# right_revision2_0.net
KiCad netlist of a schematic drawn in EAGLE
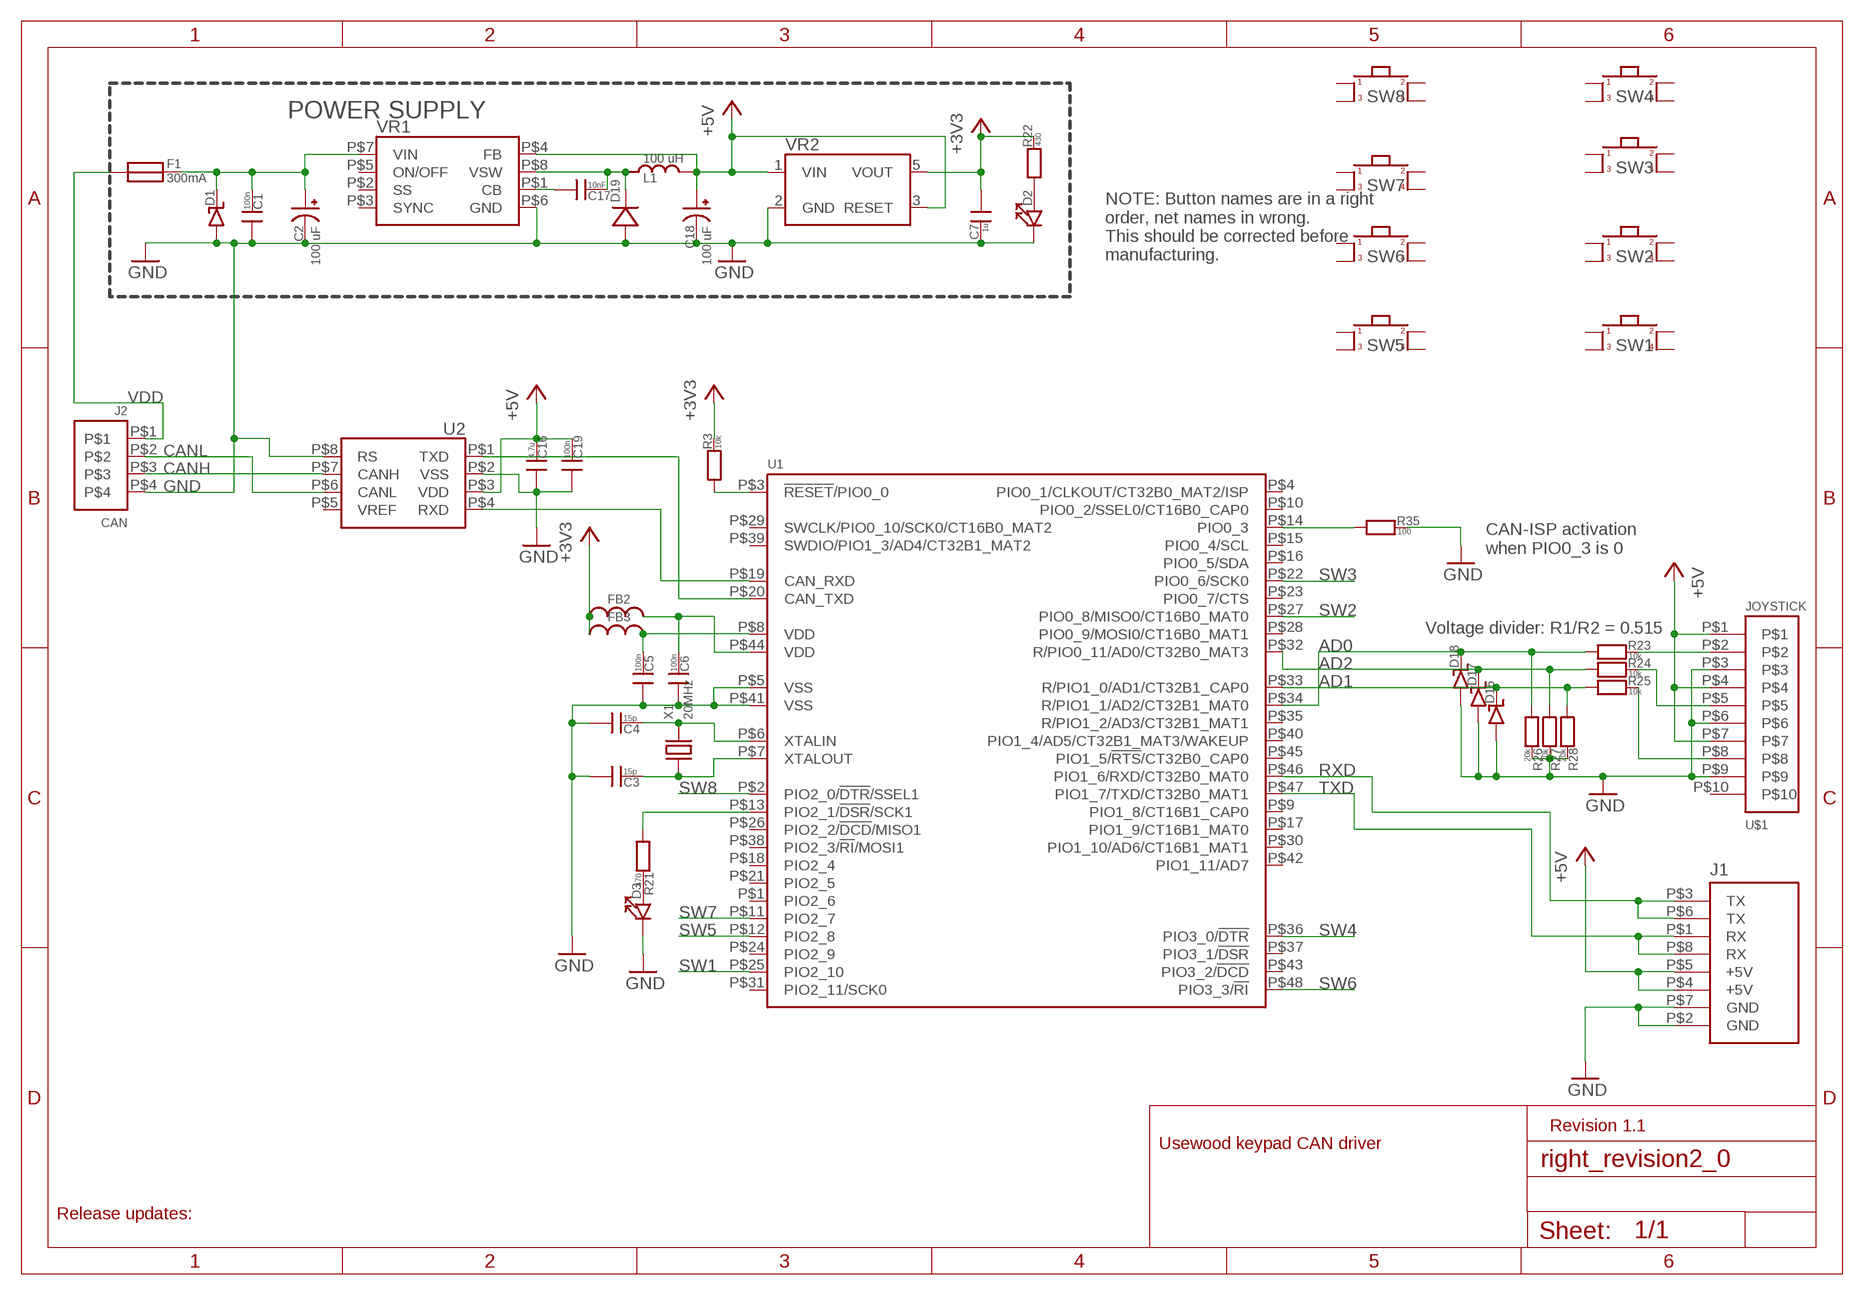
[diagram p0: schematic, sheet 1]

(export (version "E")
  (design (tool "Eeschema 10.0.6"))
  (components
    (comp (ref "C1")
      (value "100n")
      (footprint "eagle-import:0603_SILKSCREEN")
      (libsource (lib "eagle-import") (part "CAP0603_SILKSCREEN"))
    )
    (comp (ref "C2")
      (value "100 uF")
      (footprint "eagle-import:CAP_POL_SMD_10X10X10MM")
      (libsource (lib "eagle-import") (part "CAP_POLSMD_10X10X10MM"))
    )
    (comp (ref "C3")
      (value "15p")
      (footprint "eagle-import:0603_SILKSCREEN")
      (libsource (lib "eagle-import") (part "CAP0603_SILKSCREEN"))
    )
    (comp (ref "C4")
      (value "15p")
      (footprint "eagle-import:0603_SILKSCREEN")
      (libsource (lib "eagle-import") (part "CAP0603_SILKSCREEN"))
    )
    (comp (ref "C5")
      (value "100n")
      (footprint "eagle-import:0603_SILKSCREEN")
      (libsource (lib "eagle-import") (part "CAP0603_SILKSCREEN"))
    )
    (comp (ref "C6")
      (value "100n")
      (footprint "eagle-import:0603_SILKSCREEN")
      (libsource (lib "eagle-import") (part "CAP0603_SILKSCREEN"))
    )
    (comp (ref "C7")
      (value "1u")
      (footprint "eagle-import:0603_SILKSCREEN")
      (libsource (lib "eagle-import") (part "CAP0603_SILKSCREEN"))
    )
    (comp (ref "C16")
      (value "4.7u")
      (footprint "eagle-import:0603_SILKSCREEN")
      (libsource (lib "eagle-import") (part "CAP0603_SILKSCREEN"))
    )
    (comp (ref "C17")
      (value "10nF")
      (footprint "eagle-import:0603_SILKSCREEN")
      (libsource (lib "eagle-import") (part "CAP0603_SILKSCREEN"))
    )
    (comp (ref "C18")
      (value "100 uF")
      (footprint "eagle-import:CAP_POL_SMD_10X10X10MM")
      (libsource (lib "eagle-import") (part "CAP_POLSMD_10X10X10MM"))
    )
    (comp (ref "C19")
      (value "100n")
      (footprint "eagle-import:0603_SILKSCREEN")
      (libsource (lib "eagle-import") (part "CAP0603_SILKSCREEN"))
    )
    (comp (ref "D1")
      (value "DIODE_TVSDO-214AA")
      (footprint "eagle-import:DO-214AB")
      (libsource (lib "eagle-import") (part "DIODE_TVSDO-214AA"))
    )
    (comp (ref "D2")
      (value "LED0603_SILKSCREEN")
      (footprint "eagle-import:0603_SILKSCREEN")
      (libsource (lib "eagle-import") (part "LED0603_SILKSCREEN"))
    )
    (comp (ref "D3")
      (value "LED0603_SILKSCREEN")
      (footprint "eagle-import:0603_SILKSCREEN")
      (libsource (lib "eagle-import") (part "LED0603_SILKSCREEN"))
    )
    (comp (ref "D16")
      (value "DIODE_ZENERSDO123")
      (footprint "eagle-import:SOD123")
      (libsource (lib "eagle-import") (part "DIODE_ZENERSDO123"))
    )
    (comp (ref "D17")
      (value "DIODE_ZENERSDO123")
      (footprint "eagle-import:SOD123")
      (libsource (lib "eagle-import") (part "DIODE_ZENERSDO123"))
    )
    (comp (ref "D18")
      (value "DIODE_ZENERSDO123")
      (footprint "eagle-import:SOD123")
      (libsource (lib "eagle-import") (part "DIODE_ZENERSDO123"))
    )
    (comp (ref "D19")
      (value "DIODEDO219AB")
      (footprint "eagle-import:DO219AB")
      (libsource (lib "eagle-import") (part "DIODEDO219AB"))
    )
    (comp (ref "F1")
      (value "300mA")
      (footprint "eagle-import:FUSE_100MA")
      (libsource (lib "eagle-import") (part "FUSE100MA"))
    )
    (comp (ref "FB2")
      (value "FERRITE0603_SILKSCREEN")
      (footprint "eagle-import:0603_SILKSCREEN")
      (libsource (lib "eagle-import") (part "FERRITE0603_SILKSCREEN"))
    )
    (comp (ref "FB3")
      (value "FERRITE0603_SILKSCREEN")
      (footprint "eagle-import:0603_SILKSCREEN")
      (libsource (lib "eagle-import") (part "FERRITE0603_SILKSCREEN"))
    )
    (comp (ref "J1")
      (value "HEADER_USART_2_TH")
      (footprint "eagle-import:HEADER_USART_2_TH")
      (libsource (lib "eagle-import") (part "HEADER_USART_2_TH"))
    )
    (comp (ref "J2")
      (value "CAN")
      (footprint "eagle-import:MOLEX_MICRO-FIT_4WAY")
      (libsource (lib "eagle-import") (part "MOLEX_MICRO-FIT_4WAYTH"))
    )
    (comp (ref "L1")
      (value "100 uH")
      (footprint "eagle-import:INDUCTOR_BOURNS_10X13X5MM")
      (libsource (lib "eagle-import") (part "INDUCTORBOURNS_10X13X5MM"))
    )
    (comp (ref "R3")
      (value "10k")
      (footprint "eagle-import:0603_SILKSCREEN")
      (libsource (lib "eagle-import") (part "RES0604_SILKSCREEN"))
    )
    (comp (ref "R21")
      (value "470")
      (footprint "eagle-import:0603_SILKSCREEN")
      (libsource (lib "eagle-import") (part "RES0604_SILKSCREEN"))
    )
    (comp (ref "R22")
      (value "430")
      (footprint "eagle-import:0603_SILKSCREEN")
      (libsource (lib "eagle-import") (part "RES0604_SILKSCREEN"))
    )
    (comp (ref "R23")
      (value "10k")
      (footprint "eagle-import:0603_SILKSCREEN")
      (libsource (lib "eagle-import") (part "RES0604_SILKSCREEN"))
    )
    (comp (ref "R24")
      (value "10k")
      (footprint "eagle-import:0603_SILKSCREEN")
      (libsource (lib "eagle-import") (part "RES0604_SILKSCREEN"))
    )
    (comp (ref "R25")
      (value "10k")
      (footprint "eagle-import:0603_SILKSCREEN")
      (libsource (lib "eagle-import") (part "RES0604_SILKSCREEN"))
    )
    (comp (ref "R26")
      (value "20k")
      (footprint "eagle-import:0603_SILKSCREEN")
      (libsource (lib "eagle-import") (part "RES0604_SILKSCREEN"))
    )
    (comp (ref "R27")
      (value "20k")
      (footprint "eagle-import:0603_SILKSCREEN")
      (libsource (lib "eagle-import") (part "RES0604_SILKSCREEN"))
    )
    (comp (ref "R28")
      (value "20k")
      (footprint "eagle-import:0603_SILKSCREEN")
      (libsource (lib "eagle-import") (part "RES0604_SILKSCREEN"))
    )
    (comp (ref "R35")
      (value "100")
      (footprint "eagle-import:0603_SILKSCREEN")
      (libsource (lib "eagle-import") (part "RES0604_SILKSCREEN"))
    )
    (comp (ref "SW1")
      (value "SWITCH_EVQP6L")
      (footprint "eagle-import:SWITCH_EVQ9P6B40")
      (libsource (lib "eagle-import") (part "SWITCH_EVQP6L"))
    )
    (comp (ref "SW2")
      (value "SWITCH_EVQP6L")
      (footprint "eagle-import:SWITCH_EVQ9P6B40")
      (libsource (lib "eagle-import") (part "SWITCH_EVQP6L"))
    )
    (comp (ref "SW3")
      (value "SWITCH_EVQP6L")
      (footprint "eagle-import:SWITCH_EVQ9P6B40")
      (libsource (lib "eagle-import") (part "SWITCH_EVQP6L"))
    )
    (comp (ref "SW4")
      (value "SWITCH_EVQP6L")
      (footprint "eagle-import:SWITCH_EVQ9P6B40")
      (libsource (lib "eagle-import") (part "SWITCH_EVQP6L"))
    )
    (comp (ref "SW5")
      (value "SWITCH_EVQP6L")
      (footprint "eagle-import:SWITCH_EVQ9P6B40")
      (libsource (lib "eagle-import") (part "SWITCH_EVQP6L"))
    )
    (comp (ref "SW6")
      (value "SWITCH_EVQP6L")
      (footprint "eagle-import:SWITCH_EVQ9P6B40")
      (libsource (lib "eagle-import") (part "SWITCH_EVQP6L"))
    )
    (comp (ref "SW7")
      (value "SWITCH_EVQP6L")
      (footprint "eagle-import:SWITCH_EVQ9P6B40")
      (libsource (lib "eagle-import") (part "SWITCH_EVQP6L"))
    )
    (comp (ref "SW8")
      (value "SWITCH_EVQP6L")
      (footprint "eagle-import:SWITCH_EVQ9P6B40")
      (libsource (lib "eagle-import") (part "SWITCH_EVQP6L"))
    )
    (comp (ref "U$1")
      (value "JOYSTICK")
      (footprint "eagle-import:MOLEX-MICRO-FIT_10WAY")
      (libsource (lib "eagle-import") (part "MOLEX_MICRO-FIT_10WAYTH"))
    )
    (comp (ref "U1")
      (value "LPC11C14_QFP48")
      (footprint "eagle-import:QFP48")
      (libsource (lib "eagle-import") (part "LPC11C14_QFP48"))
    )
    (comp (ref "U2")
      (value "MCP2551_SOIC8")
      (footprint "eagle-import:SOIC8")
      (libsource (lib "eagle-import") (part "MCP2551_SOIC8"))
    )
    (comp (ref "VR1")
      (value "LM2671SOIC8")
      (footprint "eagle-import:SOIC8")
      (libsource (lib "eagle-import") (part "LM2671SOIC8"))
    )
    (comp (ref "VR2")
      (value "LP2985SOP5")
      (footprint "eagle-import:SOP5")
      (libsource (lib "eagle-import") (part "LP2985SOP5"))
    )
    (comp (ref "X1")
      (value "20MHz")
      (footprint "eagle-import:XTAL_SMD_5X3.2")
      (libsource (lib "eagle-import") (part "XTALSMD_5X3.2"))
    )
  )
  (nets
    (net (code "1") (name "+3V3") (class "Default")
      (node (ref "C7") (pin "0") (pinfunction "P$1_0") (pintype "bidirectional"))
      (node (ref "FB2") (pin "0") (pinfunction "P$1_0") (pintype "bidirectional"))
      (node (ref "FB3") (pin "0") (pinfunction "P$1_0") (pintype "bidirectional"))
      (node (ref "R22") (pin "1") (pinfunction "P$2_1") (pintype "bidirectional"))
      (node (ref "R3") (pin "1") (pinfunction "P$2_1") (pintype "bidirectional"))
      (node (ref "VR2") (pin "5") (pinfunction "VOUT_5") (pintype "bidirectional"))
    )
    (net (code "2") (name "+5V") (class "Default")
      (node (ref "C16") (pin "1") (pinfunction "P$2_1") (pintype "bidirectional"))
      (node (ref "C18") (pin "+") (pinfunction "+_+") (pintype "bidirectional"))
      (node (ref "C19") (pin "1") (pinfunction "P$2_1") (pintype "bidirectional"))
      (node (ref "J1") (pin "P$4") (pinfunction "+5V_P$4") (pintype "bidirectional"))
      (node (ref "J1") (pin "P$5") (pinfunction "+5V_P$5") (pintype "bidirectional"))
      (node (ref "L1") (pin "P$2") (pinfunction "P$2_P$2") (pintype "bidirectional"))
      (node (ref "U$1") (pin "P$1") (pinfunction "P$1_P$1") (pintype "bidirectional"))
      (node (ref "U$1") (pin "P$4") (pinfunction "P$4_P$4") (pintype "bidirectional"))
      (node (ref "U$1") (pin "P$7") (pinfunction "P$7_P$7") (pintype "bidirectional"))
      (node (ref "U2") (pin "P$3") (pinfunction "VDD_P$3") (pintype "bidirectional"))
      (node (ref "VR1") (pin "P$4") (pinfunction "FB_P$4") (pintype "bidirectional"))
      (node (ref "VR2") (pin "1") (pinfunction "VIN_1") (pintype "bidirectional"))
      (node (ref "VR2") (pin "3") (pinfunction "RESET_3") (pintype "bidirectional"))
    )
    (net (code "3") (name "/AD0") (class "Default")
      (node (ref "D18") (pin "P$2") (pinfunction "N_P$2") (pintype "bidirectional"))
      (node (ref "R23") (pin "0") (pinfunction "P$1_0") (pintype "bidirectional"))
      (node (ref "R26") (pin "0") (pinfunction "P$1_0") (pintype "bidirectional"))
      (node (ref "U1") (pin "P$34") (pinfunction "R/PIO1_1/AD2/CT32B1_MAT0_P$34") (pintype "bidirectional"))
    )
    (net (code "4") (name "/AD1") (class "Default")
      (node (ref "D16") (pin "P$2") (pinfunction "N_P$2") (pintype "bidirectional"))
      (node (ref "R25") (pin "0") (pinfunction "P$1_0") (pintype "bidirectional"))
      (node (ref "R28") (pin "0") (pinfunction "P$1_0") (pintype "bidirectional"))
      (node (ref "U1") (pin "P$33") (pinfunction "R/PIO1_0/AD1/CT32B1_CAP0_P$33") (pintype "bidirectional"))
    )
    (net (code "5") (name "/AD2") (class "Default")
      (node (ref "D17") (pin "P$2") (pinfunction "N_P$2") (pintype "bidirectional"))
      (node (ref "R24") (pin "0") (pinfunction "P$1_0") (pintype "bidirectional"))
      (node (ref "R27") (pin "0") (pinfunction "P$1_0") (pintype "bidirectional"))
      (node (ref "U1") (pin "P$32") (pinfunction "R/PIO0_11/AD0/CT32B0_MAT3_P$32") (pintype "bidirectional"))
    )
    (net (code "6") (name "/CANH") (class "Default")
      (node (ref "J2") (pin "P$3") (pinfunction "P$3_P$3") (pintype "bidirectional"))
      (node (ref "U2") (pin "P$7") (pinfunction "CANH_P$7") (pintype "bidirectional"))
    )
    (net (code "7") (name "/CANL") (class "Default")
      (node (ref "J2") (pin "P$2") (pinfunction "P$2_P$2") (pintype "bidirectional"))
      (node (ref "U2") (pin "P$6") (pinfunction "CANL_P$6") (pintype "bidirectional"))
    )
    (net (code "8") (name "/RXD") (class "Default")
      (node (ref "J1") (pin "P$3") (pinfunction "TX_P$3") (pintype "bidirectional"))
      (node (ref "J1") (pin "P$6") (pinfunction "TX_P$6") (pintype "bidirectional"))
      (node (ref "U1") (pin "P$46") (pinfunction "PIO1_6/RXD/CT32B0_MAT0_P$46") (pintype "bidirectional"))
    )
    (net (code "9") (name "/SW1") (class "Default")
      (node (ref "U1") (pin "P$25") (pinfunction "PIO2_10_P$25") (pintype "bidirectional"))
    )
    (net (code "10") (name "/SW2") (class "Default")
      (node (ref "U1") (pin "P$27") (pinfunction "PIO0_8/MISO0/CT16B0_MAT0_P$27") (pintype "bidirectional"))
    )
    (net (code "11") (name "/SW3") (class "Default")
      (node (ref "U1") (pin "P$22") (pinfunction "PIO0_6/SCK0_P$22") (pintype "bidirectional"))
    )
    (net (code "12") (name "/SW4") (class "Default")
      (node (ref "U1") (pin "P$36") (pinfunction "PIO3_0/~{DTR}_P$36") (pintype "bidirectional"))
    )
    (net (code "13") (name "/SW5") (class "Default")
      (node (ref "U1") (pin "P$12") (pinfunction "PIO2_8_P$12") (pintype "bidirectional"))
    )
    (net (code "14") (name "/SW6") (class "Default")
      (node (ref "U1") (pin "P$48") (pinfunction "PIO3_3/~{RI}_P$48") (pintype "bidirectional"))
    )
    (net (code "15") (name "/SW7") (class "Default")
      (node (ref "U1") (pin "P$11") (pinfunction "PIO2_7_P$11") (pintype "bidirectional"))
    )
    (net (code "16") (name "/SW8") (class "Default")
      (node (ref "U1") (pin "P$2") (pinfunction "PIO2_0/~{DTR}/SSEL1_P$2") (pintype "bidirectional"))
    )
    (net (code "17") (name "/TXD") (class "Default")
      (node (ref "J1") (pin "P$1") (pinfunction "RX_P$1") (pintype "bidirectional"))
      (node (ref "J1") (pin "P$8") (pinfunction "RX_P$8") (pintype "bidirectional"))
      (node (ref "U1") (pin "P$47") (pinfunction "PIO1_7/TXD/CT32B0_MAT1_P$47") (pintype "bidirectional"))
    )
    (net (code "18") (name "/VDD") (class "Default")
      (node (ref "F1") (pin "P$1") (pinfunction "P$1_P$1") (pintype "bidirectional"))
      (node (ref "J2") (pin "P$1") (pinfunction "P$1_P$1") (pintype "bidirectional"))
    )
    (net (code "19") (name "GND") (class "Default")
      (node (ref "C1") (pin "0") (pinfunction "P$1_0") (pintype "bidirectional"))
      (node (ref "C16") (pin "0") (pinfunction "P$1_0") (pintype "bidirectional"))
      (node (ref "C18") (pin "-") (pinfunction "-_-") (pintype "bidirectional"))
      (node (ref "C19") (pin "0") (pinfunction "P$1_0") (pintype "bidirectional"))
      (node (ref "C2") (pin "-") (pinfunction "-_-") (pintype "bidirectional"))
      (node (ref "C3") (pin "0") (pinfunction "P$1_0") (pintype "bidirectional"))
      (node (ref "C4") (pin "0") (pinfunction "P$1_0") (pintype "bidirectional"))
      (node (ref "C5") (pin "0") (pinfunction "P$1_0") (pintype "bidirectional"))
      (node (ref "C6") (pin "0") (pinfunction "P$1_0") (pintype "bidirectional"))
      (node (ref "C7") (pin "1") (pinfunction "P$2_1") (pintype "bidirectional"))
      (node (ref "D1") (pin "P$1") (pinfunction "P_P$1") (pintype "bidirectional"))
      (node (ref "D16") (pin "P$1") (pinfunction "P_P$1") (pintype "bidirectional"))
      (node (ref "D17") (pin "P$1") (pinfunction "P_P$1") (pintype "bidirectional"))
      (node (ref "D18") (pin "P$1") (pinfunction "P_P$1") (pintype "bidirectional"))
      (node (ref "D19") (pin "P$1") (pinfunction "P_P$1") (pintype "bidirectional"))
      (node (ref "D2") (pin "1") (pinfunction "1_1") (pintype "bidirectional"))
      (node (ref "D3") (pin "1") (pinfunction "1_1") (pintype "bidirectional"))
      (node (ref "J1") (pin "P$2") (pinfunction "GND_P$2") (pintype "bidirectional"))
      (node (ref "J1") (pin "P$7") (pinfunction "GND_P$7") (pintype "bidirectional"))
      (node (ref "J2") (pin "P$4") (pinfunction "P$4_P$4") (pintype "bidirectional"))
      (node (ref "R26") (pin "1") (pinfunction "P$2_1") (pintype "bidirectional"))
      (node (ref "R27") (pin "1") (pinfunction "P$2_1") (pintype "bidirectional"))
      (node (ref "R28") (pin "1") (pinfunction "P$2_1") (pintype "bidirectional"))
      (node (ref "R35") (pin "1") (pinfunction "P$2_1") (pintype "bidirectional"))
      (node (ref "U$1") (pin "P$3") (pinfunction "P$3_P$3") (pintype "bidirectional"))
      (node (ref "U$1") (pin "P$6") (pinfunction "P$6_P$6") (pintype "bidirectional"))
      (node (ref "U$1") (pin "P$9") (pinfunction "P$9_P$9") (pintype "bidirectional"))
      (node (ref "U1") (pin "P$41") (pinfunction "VSS_P$41") (pintype "bidirectional"))
      (node (ref "U1") (pin "P$5") (pinfunction "VSS_P$5") (pintype "bidirectional"))
      (node (ref "U2") (pin "P$2") (pinfunction "VSS_P$2") (pintype "bidirectional"))
      (node (ref "U2") (pin "P$8") (pinfunction "RS_P$8") (pintype "bidirectional"))
      (node (ref "VR1") (pin "P$6") (pinfunction "GND_P$6") (pintype "bidirectional"))
      (node (ref "VR2") (pin "2") (pinfunction "GND_2") (pintype "bidirectional"))
    )
    (net (code "20") (name "Net-(C1-P$2)") (class "Default")
      (node (ref "C1") (pin "1") (pinfunction "P$2_1") (pintype "bidirectional"))
      (node (ref "C2") (pin "+") (pinfunction "+_+") (pintype "bidirectional"))
      (node (ref "D1") (pin "P$2") (pinfunction "N_P$2") (pintype "bidirectional"))
      (node (ref "F1") (pin "P$2") (pinfunction "P$2_P$2") (pintype "bidirectional"))
      (node (ref "VR1") (pin "P$7") (pinfunction "VIN_P$7") (pintype "bidirectional"))
    )
    (net (code "21") (name "Net-(C3-P$2)") (class "Default")
      (node (ref "C3") (pin "1") (pinfunction "P$2_1") (pintype "bidirectional"))
      (node (ref "U1") (pin "P$7") (pinfunction "XTALOUT_P$7") (pintype "bidirectional"))
      (node (ref "X1") (pin "P$1") (pinfunction "P$1_P$1") (pintype "bidirectional"))
    )
    (net (code "22") (name "Net-(C4-P$2)") (class "Default")
      (node (ref "C4") (pin "1") (pinfunction "P$2_1") (pintype "bidirectional"))
      (node (ref "U1") (pin "P$6") (pinfunction "XTALIN_P$6") (pintype "bidirectional"))
      (node (ref "X1") (pin "P$2") (pinfunction "P$2_P$2") (pintype "bidirectional"))
    )
    (net (code "23") (name "Net-(C5-P$2)") (class "Default")
      (node (ref "C5") (pin "1") (pinfunction "P$2_1") (pintype "bidirectional"))
      (node (ref "FB3") (pin "1") (pinfunction "P$2_1") (pintype "bidirectional"))
      (node (ref "U1") (pin "P$8") (pinfunction "VDD_P$8") (pintype "bidirectional"))
    )
    (net (code "24") (name "Net-(C6-P$2)") (class "Default")
      (node (ref "C6") (pin "1") (pinfunction "P$2_1") (pintype "bidirectional"))
      (node (ref "FB2") (pin "1") (pinfunction "P$2_1") (pintype "bidirectional"))
      (node (ref "U1") (pin "P$44") (pinfunction "VDD_P$44") (pintype "bidirectional"))
    )
    (net (code "25") (name "Net-(C17-P$1)") (class "Default")
      (node (ref "C17") (pin "0") (pinfunction "P$1_0") (pintype "bidirectional"))
      (node (ref "VR1") (pin "P$1") (pinfunction "CB_P$1") (pintype "bidirectional"))
    )
    (net (code "26") (name "Net-(C17-P$2)") (class "Default")
      (node (ref "C17") (pin "1") (pinfunction "P$2_1") (pintype "bidirectional"))
      (node (ref "D19") (pin "P$2") (pinfunction "N_P$2") (pintype "bidirectional"))
      (node (ref "L1") (pin "P$1") (pinfunction "P$1_P$1") (pintype "bidirectional"))
      (node (ref "VR1") (pin "P$8") (pinfunction "VSW_P$8") (pintype "bidirectional"))
    )
    (net (code "27") (name "Net-(R3-P$1)") (class "Default")
      (node (ref "R3") (pin "0") (pinfunction "P$1_0") (pintype "bidirectional"))
      (node (ref "U1") (pin "P$3") (pinfunction "~{RESET}/PIO0_0_P$3") (pintype "bidirectional"))
    )
    (net (code "28") (name "Net-(R21-P$1)") (class "Default")
      (node (ref "R21") (pin "0") (pinfunction "P$1_0") (pintype "bidirectional"))
      (node (ref "U1") (pin "P$13") (pinfunction "PIO2_1/~{DSR}/SCK1_P$13") (pintype "bidirectional"))
    )
    (net (code "29") (name "Net-(R21-P$2)") (class "Default")
      (node (ref "D3") (pin "0") (pinfunction "0_0") (pintype "bidirectional"))
      (node (ref "R21") (pin "1") (pinfunction "P$2_1") (pintype "bidirectional"))
    )
    (net (code "30") (name "Net-(R22-P$1)") (class "Default")
      (node (ref "D2") (pin "0") (pinfunction "0_0") (pintype "bidirectional"))
      (node (ref "R22") (pin "0") (pinfunction "P$1_0") (pintype "bidirectional"))
    )
    (net (code "31") (name "Net-(R23-P$2)") (class "Default")
      (node (ref "R23") (pin "1") (pinfunction "P$2_1") (pintype "bidirectional"))
      (node (ref "U$1") (pin "P$2") (pinfunction "P$2_P$2") (pintype "bidirectional"))
    )
    (net (code "32") (name "Net-(R24-P$2)") (class "Default")
      (node (ref "R24") (pin "1") (pinfunction "P$2_1") (pintype "bidirectional"))
      (node (ref "U$1") (pin "P$5") (pinfunction "P$5_P$5") (pintype "bidirectional"))
    )
    (net (code "33") (name "Net-(R25-P$2)") (class "Default")
      (node (ref "R25") (pin "1") (pinfunction "P$2_1") (pintype "bidirectional"))
      (node (ref "U$1") (pin "P$8") (pinfunction "P$8_P$8") (pintype "bidirectional"))
    )
    (net (code "34") (name "Net-(R35-P$1)") (class "Default")
      (node (ref "R35") (pin "0") (pinfunction "P$1_0") (pintype "bidirectional"))
      (node (ref "U1") (pin "P$14") (pinfunction "PIO0_3_P$14") (pintype "bidirectional"))
    )
    (net (code "35") (name "Net-(U1-CAN_RXD)") (class "Default")
      (node (ref "U1") (pin "P$19") (pinfunction "CAN_RXD_P$19") (pintype "bidirectional"))
      (node (ref "U2") (pin "P$4") (pinfunction "RXD_P$4") (pintype "bidirectional"))
    )
    (net (code "36") (name "Net-(U1-CAN_TXD)") (class "Default")
      (node (ref "U1") (pin "P$20") (pinfunction "CAN_TXD_P$20") (pintype "bidirectional"))
      (node (ref "U2") (pin "P$1") (pinfunction "TXD_P$1") (pintype "bidirectional"))
    )
    (net (code "37") (name "unconnected-(SW1-P$1-PadA)") (class "Default")
      (node (ref "SW1") (pin "A") (pinfunction "P$1_A") (pintype "bidirectional"))
    )
    (net (code "38") (name "unconnected-(SW1-P$2-PadB)") (class "Default")
      (node (ref "SW1") (pin "B") (pinfunction "P$2_B") (pintype "bidirectional"))
    )
    (net (code "39") (name "unconnected-(SW1-P$3-PadA')") (class "Default")
      (node (ref "SW1") (pin "A'") (pinfunction "P$3_A'") (pintype "bidirectional"))
    )
    (net (code "40") (name "unconnected-(SW1-P$4-PadB')") (class "Default")
      (node (ref "SW1") (pin "B'") (pinfunction "P$4_B'") (pintype "bidirectional"))
    )
    (net (code "41") (name "unconnected-(SW2-P$1-PadA)") (class "Default")
      (node (ref "SW2") (pin "A") (pinfunction "P$1_A") (pintype "bidirectional"))
    )
    (net (code "42") (name "unconnected-(SW2-P$2-PadB)") (class "Default")
      (node (ref "SW2") (pin "B") (pinfunction "P$2_B") (pintype "bidirectional"))
    )
    (net (code "43") (name "unconnected-(SW2-P$3-PadA')") (class "Default")
      (node (ref "SW2") (pin "A'") (pinfunction "P$3_A'") (pintype "bidirectional"))
    )
    (net (code "44") (name "unconnected-(SW2-P$4-PadB')") (class "Default")
      (node (ref "SW2") (pin "B'") (pinfunction "P$4_B'") (pintype "bidirectional"))
    )
    (net (code "45") (name "unconnected-(SW3-P$1-PadA)") (class "Default")
      (node (ref "SW3") (pin "A") (pinfunction "P$1_A") (pintype "bidirectional"))
    )
    (net (code "46") (name "unconnected-(SW3-P$2-PadB)") (class "Default")
      (node (ref "SW3") (pin "B") (pinfunction "P$2_B") (pintype "bidirectional"))
    )
    (net (code "47") (name "unconnected-(SW3-P$3-PadA')") (class "Default")
      (node (ref "SW3") (pin "A'") (pinfunction "P$3_A'") (pintype "bidirectional"))
    )
    (net (code "48") (name "unconnected-(SW3-P$4-PadB')") (class "Default")
      (node (ref "SW3") (pin "B'") (pinfunction "P$4_B'") (pintype "bidirectional"))
    )
    (net (code "49") (name "unconnected-(SW4-P$1-PadA)") (class "Default")
      (node (ref "SW4") (pin "A") (pinfunction "P$1_A") (pintype "bidirectional"))
    )
    (net (code "50") (name "unconnected-(SW4-P$2-PadB)") (class "Default")
      (node (ref "SW4") (pin "B") (pinfunction "P$2_B") (pintype "bidirectional"))
    )
    (net (code "51") (name "unconnected-(SW4-P$3-PadA')") (class "Default")
      (node (ref "SW4") (pin "A'") (pinfunction "P$3_A'") (pintype "bidirectional"))
    )
    (net (code "52") (name "unconnected-(SW4-P$4-PadB')") (class "Default")
      (node (ref "SW4") (pin "B'") (pinfunction "P$4_B'") (pintype "bidirectional"))
    )
    (net (code "53") (name "unconnected-(SW5-P$1-PadA)") (class "Default")
      (node (ref "SW5") (pin "A") (pinfunction "P$1_A") (pintype "bidirectional"))
    )
    (net (code "54") (name "unconnected-(SW5-P$2-PadB)") (class "Default")
      (node (ref "SW5") (pin "B") (pinfunction "P$2_B") (pintype "bidirectional"))
    )
    (net (code "55") (name "unconnected-(SW5-P$3-PadA')") (class "Default")
      (node (ref "SW5") (pin "A'") (pinfunction "P$3_A'") (pintype "bidirectional"))
    )
    (net (code "56") (name "unconnected-(SW5-P$4-PadB')") (class "Default")
      (node (ref "SW5") (pin "B'") (pinfunction "P$4_B'") (pintype "bidirectional"))
    )
    (net (code "57") (name "unconnected-(SW6-P$1-PadA)") (class "Default")
      (node (ref "SW6") (pin "A") (pinfunction "P$1_A") (pintype "bidirectional"))
    )
    (net (code "58") (name "unconnected-(SW6-P$2-PadB)") (class "Default")
      (node (ref "SW6") (pin "B") (pinfunction "P$2_B") (pintype "bidirectional"))
    )
    (net (code "59") (name "unconnected-(SW6-P$3-PadA')") (class "Default")
      (node (ref "SW6") (pin "A'") (pinfunction "P$3_A'") (pintype "bidirectional"))
    )
    (net (code "60") (name "unconnected-(SW6-P$4-PadB')") (class "Default")
      (node (ref "SW6") (pin "B'") (pinfunction "P$4_B'") (pintype "bidirectional"))
    )
    (net (code "61") (name "unconnected-(SW7-P$1-PadA)") (class "Default")
      (node (ref "SW7") (pin "A") (pinfunction "P$1_A") (pintype "bidirectional"))
    )
    (net (code "62") (name "unconnected-(SW7-P$2-PadB)") (class "Default")
      (node (ref "SW7") (pin "B") (pinfunction "P$2_B") (pintype "bidirectional"))
    )
    (net (code "63") (name "unconnected-(SW7-P$3-PadA')") (class "Default")
      (node (ref "SW7") (pin "A'") (pinfunction "P$3_A'") (pintype "bidirectional"))
    )
    (net (code "64") (name "unconnected-(SW7-P$4-PadB')") (class "Default")
      (node (ref "SW7") (pin "B'") (pinfunction "P$4_B'") (pintype "bidirectional"))
    )
    (net (code "65") (name "unconnected-(SW8-P$1-PadA)") (class "Default")
      (node (ref "SW8") (pin "A") (pinfunction "P$1_A") (pintype "bidirectional"))
    )
    (net (code "66") (name "unconnected-(SW8-P$2-PadB)") (class "Default")
      (node (ref "SW8") (pin "B") (pinfunction "P$2_B") (pintype "bidirectional"))
    )
    (net (code "67") (name "unconnected-(SW8-P$3-PadA')") (class "Default")
      (node (ref "SW8") (pin "A'") (pinfunction "P$3_A'") (pintype "bidirectional"))
    )
    (net (code "68") (name "unconnected-(SW8-P$4-PadB')") (class "Default")
      (node (ref "SW8") (pin "B'") (pinfunction "P$4_B'") (pintype "bidirectional"))
    )
    (net (code "69") (name "unconnected-(U$1-PadP$10)") (class "Default")
      (node (ref "U$1") (pin "P$10") (pinfunction "P$10_P$10") (pintype "bidirectional"))
    )
    (net (code "70") (name "unconnected-(U1-PIO0_1{slash}CLKOUT{slash}CT32B0_MAT2{slash}ISP-PadP$4)") (class "Default")
      (node (ref "U1") (pin "P$4") (pinfunction "PIO0_1/CLKOUT/CT32B0_MAT2/ISP_P$4") (pintype "bidirectional"))
    )
    (net (code "71") (name "unconnected-(U1-PIO0_2{slash}SSEL0{slash}CT16B0_CAP0-PadP$10)") (class "Default")
      (node (ref "U1") (pin "P$10") (pinfunction "PIO0_2/SSEL0/CT16B0_CAP0_P$10") (pintype "bidirectional"))
    )
    (net (code "72") (name "unconnected-(U1-PIO0_4{slash}SCL-PadP$15)") (class "Default")
      (node (ref "U1") (pin "P$15") (pinfunction "PIO0_4/SCL_P$15") (pintype "bidirectional"))
    )
    (net (code "73") (name "unconnected-(U1-PIO0_5{slash}SDA-PadP$16)") (class "Default")
      (node (ref "U1") (pin "P$16") (pinfunction "PIO0_5/SDA_P$16") (pintype "bidirectional"))
    )
    (net (code "74") (name "unconnected-(U1-PIO0_7{slash}CTS-PadP$23)") (class "Default")
      (node (ref "U1") (pin "P$23") (pinfunction "PIO0_7/CTS_P$23") (pintype "bidirectional"))
    )
    (net (code "75") (name "unconnected-(U1-PIO0_9{slash}MOSI0{slash}CT16B0_MAT1-PadP$28)") (class "Default")
      (node (ref "U1") (pin "P$28") (pinfunction "PIO0_9/MOSI0/CT16B0_MAT1_P$28") (pintype "bidirectional"))
    )
    (net (code "76") (name "unconnected-(U1-PIO1_4{slash}AD5{slash}CT32B1_MAT3{slash}WAKEUP-PadP$40)") (class "Default")
      (node (ref "U1") (pin "P$40") (pinfunction "PIO1_4/AD5/CT32B1_MAT3/WAKEUP_P$40") (pintype "bidirectional"))
    )
    (net (code "77") (name "unconnected-(U1-PIO1_5{slash}~{RTS}{slash}CT32B0_CAP0-PadP$45)") (class "Default")
      (node (ref "U1") (pin "P$45") (pinfunction "PIO1_5/~{RTS}/CT32B0_CAP0_P$45") (pintype "bidirectional"))
    )
    (net (code "78") (name "unconnected-(U1-PIO1_8{slash}CT16B1_CAP0-PadP$9)") (class "Default")
      (node (ref "U1") (pin "P$9") (pinfunction "PIO1_8/CT16B1_CAP0_P$9") (pintype "bidirectional"))
    )
    (net (code "79") (name "unconnected-(U1-PIO1_9{slash}CT16B1_MAT0-PadP$17)") (class "Default")
      (node (ref "U1") (pin "P$17") (pinfunction "PIO1_9/CT16B1_MAT0_P$17") (pintype "bidirectional"))
    )
    (net (code "80") (name "unconnected-(U1-PIO1_10{slash}AD6{slash}CT16B1_MAT1-PadP$30)") (class "Default")
      (node (ref "U1") (pin "P$30") (pinfunction "PIO1_10/AD6/CT16B1_MAT1_P$30") (pintype "bidirectional"))
    )
    (net (code "81") (name "unconnected-(U1-PIO1_11{slash}AD7-PadP$42)") (class "Default")
      (node (ref "U1") (pin "P$42") (pinfunction "PIO1_11/AD7_P$42") (pintype "bidirectional"))
    )
    (net (code "82") (name "unconnected-(U1-PIO2_2{slash}~{DCD}{slash}MISO1-PadP$26)") (class "Default")
      (node (ref "U1") (pin "P$26") (pinfunction "PIO2_2/~{DCD}/MISO1_P$26") (pintype "bidirectional"))
    )
    (net (code "83") (name "unconnected-(U1-PIO2_3{slash}~{RI}{slash}MOSI1-PadP$38)") (class "Default")
      (node (ref "U1") (pin "P$38") (pinfunction "PIO2_3/~{RI}/MOSI1_P$38") (pintype "bidirectional"))
    )
    (net (code "84") (name "unconnected-(U1-PIO2_4-PadP$18)") (class "Default")
      (node (ref "U1") (pin "P$18") (pinfunction "PIO2_4_P$18") (pintype "bidirectional"))
    )
    (net (code "85") (name "unconnected-(U1-PIO2_5-PadP$21)") (class "Default")
      (node (ref "U1") (pin "P$21") (pinfunction "PIO2_5_P$21") (pintype "bidirectional"))
    )
    (net (code "86") (name "unconnected-(U1-PIO2_6-PadP$1)") (class "Default")
      (node (ref "U1") (pin "P$1") (pinfunction "PIO2_6_P$1") (pintype "bidirectional"))
    )
    (net (code "87") (name "unconnected-(U1-PIO2_9-PadP$24)") (class "Default")
      (node (ref "U1") (pin "P$24") (pinfunction "PIO2_9_P$24") (pintype "bidirectional"))
    )
    (net (code "88") (name "unconnected-(U1-PIO2_11{slash}SCK0-PadP$31)") (class "Default")
      (node (ref "U1") (pin "P$31") (pinfunction "PIO2_11/SCK0_P$31") (pintype "bidirectional"))
    )
    (net (code "89") (name "unconnected-(U1-PIO3_1{slash}~{DSR}-PadP$37)") (class "Default")
      (node (ref "U1") (pin "P$37") (pinfunction "PIO3_1/~{DSR}_P$37") (pintype "bidirectional"))
    )
    (net (code "90") (name "unconnected-(U1-PIO3_2{slash}~{DCD}-PadP$43)") (class "Default")
      (node (ref "U1") (pin "P$43") (pinfunction "PIO3_2/~{DCD}_P$43") (pintype "bidirectional"))
    )
    (net (code "91") (name "unconnected-(U1-R{slash}PIO1_2{slash}AD3{slash}CT32B1_MAT1-PadP$35)") (class "Default")
      (node (ref "U1") (pin "P$35") (pinfunction "R/PIO1_2/AD3/CT32B1_MAT1_P$35") (pintype "bidirectional"))
    )
    (net (code "92") (name "unconnected-(U1-SWCLK{slash}PIO0_10{slash}SCK0{slash}CT16B0_MAT2-PadP$29)") (class "Default")
      (node (ref "U1") (pin "P$29") (pinfunction "SWCLK/PIO0_10/SCK0/CT16B0_MAT2_P$29") (pintype "bidirectional"))
    )
    (net (code "93") (name "unconnected-(U1-SWDIO{slash}PIO1_3{slash}AD4{slash}CT32B1_MAT2-PadP$39)") (class "Default")
      (node (ref "U1") (pin "P$39") (pinfunction "SWDIO/PIO1_3/AD4/CT32B1_MAT2_P$39") (pintype "bidirectional"))
    )
    (net (code "94") (name "unconnected-(U2-VREF-PadP$5)") (class "Default")
      (node (ref "U2") (pin "P$5") (pinfunction "VREF_P$5") (pintype "bidirectional"))
    )
    (net (code "95") (name "unconnected-(VR1-ON{slash}OFF-PadP$5)") (class "Default")
      (node (ref "VR1") (pin "P$5") (pinfunction "ON/OFF_P$5") (pintype "bidirectional"))
    )
    (net (code "96") (name "unconnected-(VR1-SS-PadP$2)") (class "Default")
      (node (ref "VR1") (pin "P$2") (pinfunction "SS_P$2") (pintype "bidirectional"))
    )
    (net (code "97") (name "unconnected-(VR1-SYNC-PadP$3)") (class "Default")
      (node (ref "VR1") (pin "P$3") (pinfunction "SYNC_P$3") (pintype "bidirectional"))
    )
  )
)
